# ESP8266_SMD_0603.net
KiCad netlist of a schematic drawn in EAGLE
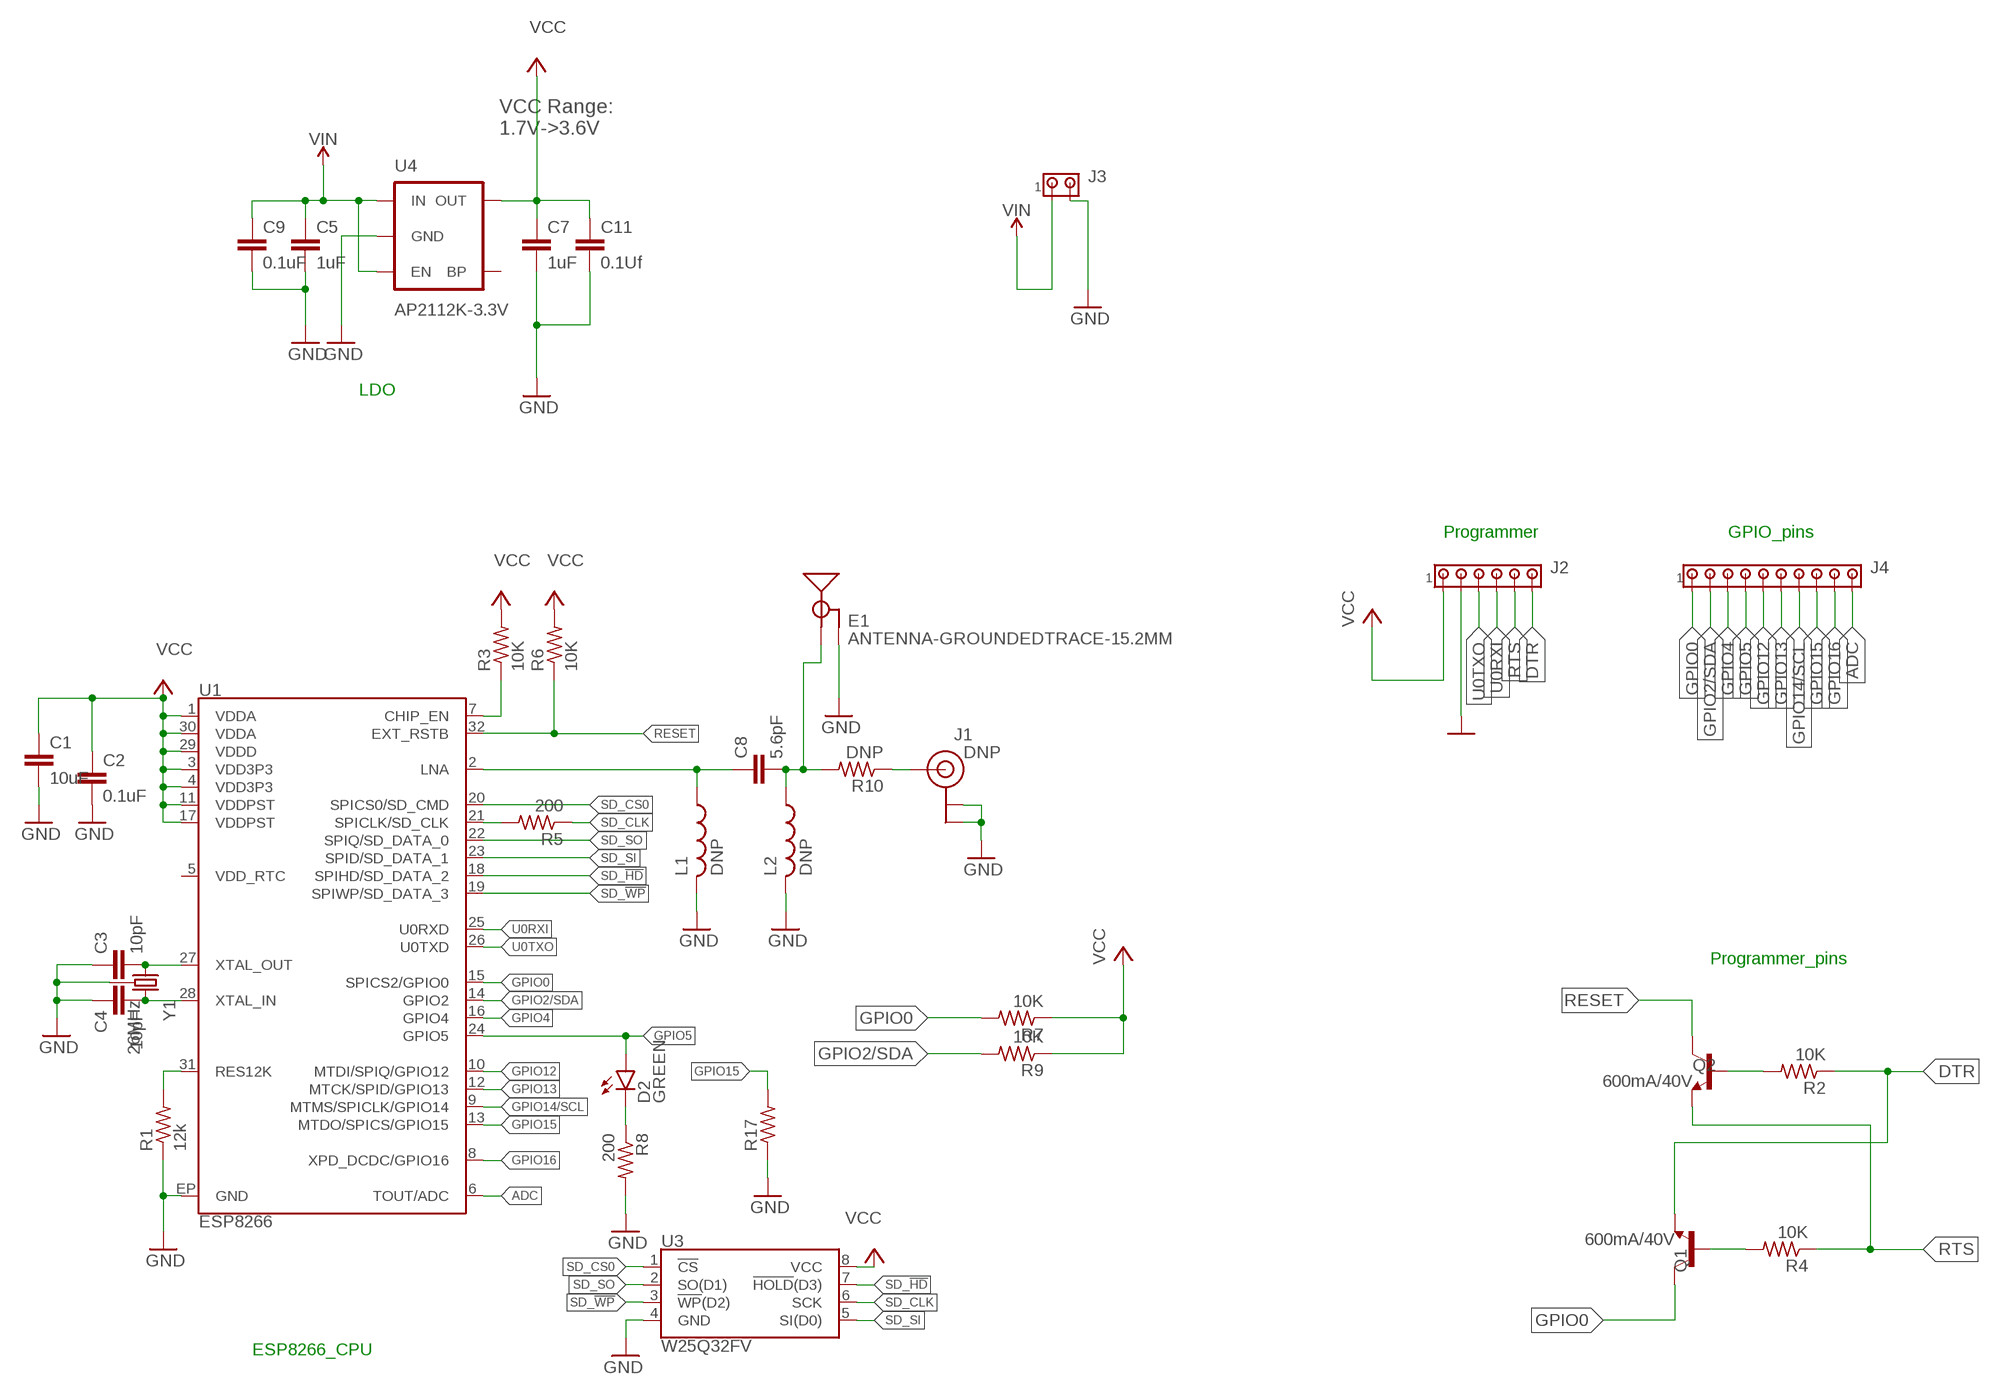
[diagram p0: schematic, sheet 1]

(export (version "E")
  (design (tool "Eeschema 10.0.6"))
  (components
    (comp (ref "C1")
      (value "10uF")
      (footprint "eagle-import:C0603")
      (libsource (lib "eagle-import") (part "resistor_C-EUC0603"))
    )
    (comp (ref "C2")
      (value "0.1uF")
      (footprint "eagle-import:C0603")
      (libsource (lib "eagle-import") (part "resistor_C-EUC0603"))
    )
    (comp (ref "C3")
      (value "10pF")
      (footprint "eagle-import:C0603")
      (libsource (lib "eagle-import") (part "C-EUC0603"))
    )
    (comp (ref "C4")
      (value "10pF")
      (footprint "eagle-import:C0603")
      (libsource (lib "eagle-import") (part "C-EUC0603"))
    )
    (comp (ref "C5")
      (value "1uF")
      (footprint "eagle-import:C0603")
      (libsource (lib "eagle-import") (part "C-EUC0603"))
    )
    (comp (ref "C7")
      (value "1uF")
      (footprint "eagle-import:C0603")
      (libsource (lib "eagle-import") (part "C-EUC0603"))
    )
    (comp (ref "C8")
      (value "5.6pF")
      (footprint "eagle-import:C0603")
      (libsource (lib "eagle-import") (part "C-EUC0603"))
    )
    (comp (ref "C9")
      (value "0.1uF")
      (footprint "eagle-import:C0603")
      (libsource (lib "eagle-import") (part "C-EUC0603"))
    )
    (comp (ref "C11")
      (value "0.1Uf")
      (footprint "eagle-import:C0603")
      (libsource (lib "eagle-import") (part "C-EUC0603"))
    )
    (comp (ref "D2")
      (value "GREEN")
      (footprint "eagle-import:LED-0603")
      (libsource (lib "eagle-import") (part "LED-GREEN0603"))
    )
    (comp (ref "E1")
      (value "ANTENNA-GROUNDEDTRACE-15.2MM")
      (footprint "eagle-import:TRACE_ANTENNA_2.4GHZ_15.2MM")
      (libsource (lib "eagle-import") (part "ANTENNA-GROUNDEDTRACE-15.2MM"))
    )
    (comp (ref "J1")
      (value "DNP")
      (footprint "eagle-import:U.FL")
      (libsource (lib "eagle-import") (part "U.FL"))
    )
    (comp (ref "J2")
      (value "MTA06-100")
      (footprint "eagle-import:10X06MTA")
      (libsource (lib "eagle-import") (part "MTA06-100"))
    )
    (comp (ref "J3")
      (value "MTA02-100")
      (footprint "eagle-import:10X02MTA")
      (libsource (lib "eagle-import") (part "MTA02-100"))
    )
    (comp (ref "J4")
      (value "MTA10-100")
      (footprint "eagle-import:10X10MTA")
      (libsource (lib "eagle-import") (part "MTA10-100"))
    )
    (comp (ref "L1")
      (value "DNP")
      (footprint "eagle-import:L0603")
      (libsource (lib "eagle-import") (part "L-USL0603"))
    )
    (comp (ref "L2")
      (value "DNP")
      (footprint "eagle-import:L0603")
      (libsource (lib "eagle-import") (part "L-USL0603"))
    )
    (comp (ref "Q1")
      (value "600mA/40V")
      (footprint "eagle-import:SOT23-3")
      (libsource (lib "eagle-import") (part "TRANS_NPN-MMBT2222AL"))
    )
    (comp (ref "Q2")
      (value "600mA/40V")
      (footprint "eagle-import:SOT23-3")
      (libsource (lib "eagle-import") (part "TRANS_NPN-MMBT2222AL"))
    )
    (comp (ref "R1")
      (value "12k")
      (footprint "eagle-import:R0603")
      (libsource (lib "eagle-import") (part "R-US_R0603"))
    )
    (comp (ref "R2")
      (value "10K")
      (footprint "eagle-import:R0603")
      (libsource (lib "eagle-import") (part "R-US_R0603"))
    )
    (comp (ref "R3")
      (value "10K")
      (footprint "eagle-import:R0603")
      (libsource (lib "eagle-import") (part "R-US_R0603"))
    )
    (comp (ref "R4")
      (value "10K")
      (footprint "eagle-import:R0603")
      (libsource (lib "eagle-import") (part "R-US_R0603"))
    )
    (comp (ref "R5")
      (value "200")
      (footprint "eagle-import:R0603")
      (libsource (lib "eagle-import") (part "R-US_R0603"))
    )
    (comp (ref "R6")
      (value "10K")
      (footprint "eagle-import:R0603")
      (libsource (lib "eagle-import") (part "R-US_R0603"))
    )
    (comp (ref "R7")
      (value "10K")
      (footprint "eagle-import:R0603")
      (libsource (lib "eagle-import") (part "R-US_R0603"))
    )
    (comp (ref "R8")
      (value "200")
      (footprint "eagle-import:R0603")
      (libsource (lib "eagle-import") (part "R-US_R0603"))
    )
    (comp (ref "R9")
      (value "10K")
      (footprint "eagle-import:R0603")
      (libsource (lib "eagle-import") (part "R-US_R0603"))
    )
    (comp (ref "R10")
      (value "DNP")
      (footprint "eagle-import:R0603")
      (libsource (lib "eagle-import") (part "R-US_R0603"))
    )
    (comp (ref "R17")
      (value "10K")
      (footprint "eagle-import:R0603")
      (libsource (lib "eagle-import") (part "R-US_R0603"))
    )
    (comp (ref "U1")
      (value "ESP8266")
      (footprint "eagle-import:QFN32")
      (libsource (lib "eagle-import") (part "ESP8266"))
    )
    (comp (ref "U3")
      (value "W25Q32FV")
      (footprint "eagle-import:SOIC-8")
      (libsource (lib "eagle-import") (part "W25Q32FVSS"))
    )
    (comp (ref "U4")
      (value "AP2112K-3.3V")
      (footprint "eagle-import:SOT23-5")
      (libsource (lib "eagle-import") (part "V_REG_LDOSMD"))
    )
    (comp (ref "Y1")
      (value "26MHz")
      (footprint "eagle-import:CRYSTAL-SMD-3.2X2.5")
      (libsource (lib "eagle-import") (part "CRYSTAL-GROUNDED3.2X2.5"))
    )
  )
  (nets
    (net (code "1") (name "/SD_~{HD}") (class "Default")
      (node (ref "U1") (pin "18") (pinfunction "SPIHD/SD_DATA_2_18") (pintype "bidirectional"))
      (node (ref "U3") (pin "7") (pinfunction "~{HOLD}(D3)_7") (pintype "bidirectional"))
    )
    (net (code "2") (name "/SD_~{WP}") (class "Default")
      (node (ref "U1") (pin "19") (pinfunction "SPIWP/SD_DATA_3_19") (pintype "bidirectional"))
      (node (ref "U3") (pin "3") (pinfunction "~{WP}(D2)_3") (pintype "bidirectional"))
    )
    (net (code "3") (name "ADC") (class "Default")
      (node (ref "J4") (pin "10") (pinfunction "10_10") (pintype "passive"))
      (node (ref "U1") (pin "6") (pinfunction "TOUT/ADC_6") (pintype "bidirectional"))
    )
    (net (code "4") (name "DTR") (class "Default")
      (node (ref "J2") (pin "6") (pinfunction "6_6") (pintype "passive"))
      (node (ref "Q1") (pin "2") (pinfunction "E_2") (pintype "passive"))
      (node (ref "R2") (pin "1") (pinfunction "1_1") (pintype "passive"))
    )
    (net (code "5") (name "GND") (class "Default")
      (node (ref "C1") (pin "2") (pinfunction "2_2") (pintype "passive"))
      (node (ref "C11") (pin "2") (pinfunction "2_2") (pintype "passive"))
      (node (ref "C2") (pin "2") (pinfunction "2_2") (pintype "passive"))
      (node (ref "C3") (pin "1") (pinfunction "1_1") (pintype "passive"))
      (node (ref "C4") (pin "1") (pinfunction "1_1") (pintype "passive"))
      (node (ref "C5") (pin "2") (pinfunction "2_2") (pintype "passive"))
      (node (ref "C7") (pin "2") (pinfunction "2_2") (pintype "passive"))
      (node (ref "C9") (pin "2") (pinfunction "2_2") (pintype "passive"))
      (node (ref "E1") (pin "GND") (pinfunction "GND_GND") (pintype "bidirectional"))
      (node (ref "J1") (pin "P$1") (pinfunction "GND_P$1") (pintype "bidirectional"))
      (node (ref "J1") (pin "P$2") (pinfunction "GND_P$2") (pintype "bidirectional"))
      (node (ref "J2") (pin "2") (pinfunction "2_2") (pintype "passive"))
      (node (ref "J3") (pin "2") (pinfunction "2_2") (pintype "passive"))
      (node (ref "L1") (pin "2") (pinfunction "2_2") (pintype "passive"))
      (node (ref "L2") (pin "2") (pinfunction "2_2") (pintype "passive"))
      (node (ref "R1") (pin "1") (pinfunction "1_1") (pintype "passive"))
      (node (ref "R17") (pin "1") (pinfunction "1_1") (pintype "passive"))
      (node (ref "R8") (pin "2") (pinfunction "2_2") (pintype "passive"))
      (node (ref "U1") (pin "EP") (pinfunction "GND_EP") (pintype "bidirectional"))
      (node (ref "U3") (pin "4") (pinfunction "GND_4") (pintype "bidirectional"))
      (node (ref "U4") (pin "2") (pinfunction "GND_2") (pintype "input"))
      (node (ref "Y1") (pin "2") (pinfunction "GND_2") (pintype "passive"))
      (node (ref "Y1") (pin "4") (pinfunction "GND_4") (pintype "passive"))
    )
    (net (code "6") (name "GPIO0") (class "Default")
      (node (ref "J4") (pin "1") (pinfunction "1_1") (pintype "passive"))
      (node (ref "Q1") (pin "3") (pinfunction "C_3") (pintype "passive"))
      (node (ref "R7") (pin "2") (pinfunction "2_2") (pintype "passive"))
      (node (ref "U1") (pin "15") (pinfunction "SPICS2/GPIO0_15") (pintype "bidirectional"))
    )
    (net (code "7") (name "GPIO2{slash}SDA") (class "Default")
      (node (ref "J4") (pin "2") (pinfunction "2_2") (pintype "passive"))
      (node (ref "R9") (pin "2") (pinfunction "2_2") (pintype "passive"))
      (node (ref "U1") (pin "14") (pinfunction "GPIO2_14") (pintype "bidirectional"))
    )
    (net (code "8") (name "GPIO4") (class "Default")
      (node (ref "J4") (pin "3") (pinfunction "3_3") (pintype "passive"))
      (node (ref "U1") (pin "16") (pinfunction "GPIO4_16") (pintype "bidirectional"))
    )
    (net (code "9") (name "GPIO5") (class "Default")
      (node (ref "D2") (pin "A") (pinfunction "A_A") (pintype "passive"))
      (node (ref "J4") (pin "4") (pinfunction "4_4") (pintype "passive"))
      (node (ref "U1") (pin "24") (pinfunction "GPIO5_24") (pintype "bidirectional"))
    )
    (net (code "10") (name "GPIO12") (class "Default")
      (node (ref "J4") (pin "5") (pinfunction "5_5") (pintype "passive"))
      (node (ref "U1") (pin "10") (pinfunction "MTDI/SPIQ/GPIO12_10") (pintype "bidirectional"))
    )
    (net (code "11") (name "GPIO13") (class "Default")
      (node (ref "J4") (pin "6") (pinfunction "6_6") (pintype "passive"))
      (node (ref "U1") (pin "12") (pinfunction "MTCK/SPID/GPIO13_12") (pintype "bidirectional"))
    )
    (net (code "12") (name "GPIO14{slash}SCL") (class "Default")
      (node (ref "J4") (pin "7") (pinfunction "7_7") (pintype "passive"))
      (node (ref "U1") (pin "9") (pinfunction "MTMS/SPICLK/GPIO14_9") (pintype "bidirectional"))
    )
    (net (code "13") (name "GPIO15") (class "Default")
      (node (ref "J4") (pin "8") (pinfunction "8_8") (pintype "passive"))
      (node (ref "R17") (pin "2") (pinfunction "2_2") (pintype "passive"))
      (node (ref "U1") (pin "13") (pinfunction "MTDO/SPICS/GPIO15_13") (pintype "bidirectional"))
    )
    (net (code "14") (name "GPIO16") (class "Default")
      (node (ref "J4") (pin "9") (pinfunction "9_9") (pintype "passive"))
      (node (ref "U1") (pin "8") (pinfunction "XPD_DCDC/GPIO16_8") (pintype "bidirectional"))
    )
    (net (code "15") (name "Net-(D2-PadC)") (class "Default")
      (node (ref "D2") (pin "C") (pinfunction "C_C") (pintype "passive"))
      (node (ref "R8") (pin "1") (pinfunction "1_1") (pintype "passive"))
    )
    (net (code "16") (name "Net-(E1-SIGNAL)") (class "Default")
      (node (ref "C8") (pin "2") (pinfunction "2_2") (pintype "passive"))
      (node (ref "E1") (pin "ANT") (pinfunction "SIGNAL_ANT") (pintype "bidirectional"))
      (node (ref "L2") (pin "1") (pinfunction "1_1") (pintype "passive"))
      (node (ref "R10") (pin "2") (pinfunction "2_2") (pintype "passive"))
    )
    (net (code "17") (name "Net-(J1-SIGNAL)") (class "Default")
      (node (ref "J1") (pin "P$3") (pinfunction "SIGNAL_P$3") (pintype "bidirectional"))
      (node (ref "R10") (pin "1") (pinfunction "1_1") (pintype "passive"))
    )
    (net (code "18") (name "Net-(Q1-B)") (class "Default")
      (node (ref "Q1") (pin "1") (pinfunction "B_1") (pintype "passive"))
      (node (ref "R4") (pin "2") (pinfunction "2_2") (pintype "passive"))
    )
    (net (code "19") (name "Net-(Q2-B)") (class "Default")
      (node (ref "Q2") (pin "1") (pinfunction "B_1") (pintype "passive"))
      (node (ref "R2") (pin "2") (pinfunction "2_2") (pintype "passive"))
    )
    (net (code "20") (name "Net-(U1-CHIP_EN)") (class "Default")
      (node (ref "R3") (pin "1") (pinfunction "1_1") (pintype "passive"))
      (node (ref "U1") (pin "7") (pinfunction "CHIP_EN_7") (pintype "bidirectional"))
    )
    (net (code "21") (name "Net-(U1-LNA)") (class "Default")
      (node (ref "C8") (pin "1") (pinfunction "1_1") (pintype "passive"))
      (node (ref "L1") (pin "1") (pinfunction "1_1") (pintype "passive"))
      (node (ref "U1") (pin "2") (pinfunction "LNA_2") (pintype "bidirectional"))
    )
    (net (code "22") (name "Net-(U1-RES12K)") (class "Default")
      (node (ref "R1") (pin "2") (pinfunction "2_2") (pintype "passive"))
      (node (ref "U1") (pin "31") (pinfunction "RES12K_31") (pintype "bidirectional"))
    )
    (net (code "23") (name "Net-(U1-SPICLK{slash}SD_CLK)") (class "Default")
      (node (ref "R5") (pin "2") (pinfunction "2_2") (pintype "passive"))
      (node (ref "U1") (pin "21") (pinfunction "SPICLK/SD_CLK_21") (pintype "bidirectional"))
    )
    (net (code "24") (name "Net-(U1-XTAL_IN)") (class "Default")
      (node (ref "C4") (pin "2") (pinfunction "2_2") (pintype "passive"))
      (node (ref "U1") (pin "28") (pinfunction "XTAL_IN_28") (pintype "bidirectional"))
      (node (ref "Y1") (pin "3") (pinfunction "2_3") (pintype "passive"))
    )
    (net (code "25") (name "Net-(U1-XTAL_OUT)") (class "Default")
      (node (ref "C3") (pin "2") (pinfunction "2_2") (pintype "passive"))
      (node (ref "U1") (pin "27") (pinfunction "XTAL_OUT_27") (pintype "bidirectional"))
      (node (ref "Y1") (pin "1") (pinfunction "1_1") (pintype "passive"))
    )
    (net (code "26") (name "RESET") (class "Default")
      (node (ref "Q2") (pin "3") (pinfunction "C_3") (pintype "passive"))
      (node (ref "R6") (pin "1") (pinfunction "1_1") (pintype "passive"))
      (node (ref "U1") (pin "32") (pinfunction "EXT_RSTB_32") (pintype "bidirectional"))
    )
    (net (code "27") (name "RTS") (class "Default")
      (node (ref "J2") (pin "5") (pinfunction "5_5") (pintype "passive"))
      (node (ref "Q2") (pin "2") (pinfunction "E_2") (pintype "passive"))
      (node (ref "R4") (pin "1") (pinfunction "1_1") (pintype "passive"))
    )
    (net (code "28") (name "SD_CLK") (class "Default")
      (node (ref "R5") (pin "1") (pinfunction "1_1") (pintype "passive"))
      (node (ref "U3") (pin "6") (pinfunction "SCK_6") (pintype "bidirectional"))
    )
    (net (code "29") (name "SD_CS0") (class "Default")
      (node (ref "U1") (pin "20") (pinfunction "SPICS0/SD_CMD_20") (pintype "bidirectional"))
      (node (ref "U3") (pin "1") (pinfunction "~{CS}_1") (pintype "bidirectional"))
    )
    (net (code "30") (name "SD_SI") (class "Default")
      (node (ref "U1") (pin "23") (pinfunction "SPID/SD_DATA_1_23") (pintype "bidirectional"))
      (node (ref "U3") (pin "5") (pinfunction "SI(D0)_5") (pintype "bidirectional"))
    )
    (net (code "31") (name "SD_SO") (class "Default")
      (node (ref "U1") (pin "22") (pinfunction "SPIQ/SD_DATA_0_22") (pintype "bidirectional"))
      (node (ref "U3") (pin "2") (pinfunction "SO(D1)_2") (pintype "bidirectional"))
    )
    (net (code "32") (name "U0RXI") (class "Default")
      (node (ref "J2") (pin "4") (pinfunction "4_4") (pintype "passive"))
      (node (ref "U1") (pin "25") (pinfunction "U0RXD_25") (pintype "bidirectional"))
    )
    (net (code "33") (name "U0TXO") (class "Default")
      (node (ref "J2") (pin "3") (pinfunction "3_3") (pintype "passive"))
      (node (ref "U1") (pin "26") (pinfunction "U0TXD_26") (pintype "bidirectional"))
    )
    (net (code "34") (name "VCC") (class "Default")
      (node (ref "C1") (pin "1") (pinfunction "1_1") (pintype "passive"))
      (node (ref "C11") (pin "1") (pinfunction "1_1") (pintype "passive"))
      (node (ref "C2") (pin "1") (pinfunction "1_1") (pintype "passive"))
      (node (ref "C7") (pin "1") (pinfunction "1_1") (pintype "passive"))
      (node (ref "J2") (pin "1") (pinfunction "1_1") (pintype "passive"))
      (node (ref "R3") (pin "2") (pinfunction "2_2") (pintype "passive"))
      (node (ref "R6") (pin "2") (pinfunction "2_2") (pintype "passive"))
      (node (ref "R7") (pin "1") (pinfunction "1_1") (pintype "passive"))
      (node (ref "R9") (pin "1") (pinfunction "1_1") (pintype "passive"))
      (node (ref "U1") (pin "1") (pinfunction "VDDA_1") (pintype "bidirectional"))
      (node (ref "U1") (pin "11") (pinfunction "VDDPST_11") (pintype "bidirectional"))
      (node (ref "U1") (pin "17") (pinfunction "VDDPST_17") (pintype "bidirectional"))
      (node (ref "U1") (pin "29") (pinfunction "VDDD_29") (pintype "bidirectional"))
      (node (ref "U1") (pin "3") (pinfunction "VDD3P3_3") (pintype "bidirectional"))
      (node (ref "U1") (pin "30") (pinfunction "VDDA_30") (pintype "bidirectional"))
      (node (ref "U1") (pin "4") (pinfunction "VDD3P3_4") (pintype "bidirectional"))
      (node (ref "U3") (pin "8") (pinfunction "VCC_8") (pintype "bidirectional"))
      (node (ref "U4") (pin "5") (pinfunction "OUT_5") (pintype "passive"))
    )
    (net (code "35") (name "VIN") (class "Default")
      (node (ref "C5") (pin "1") (pinfunction "1_1") (pintype "passive"))
      (node (ref "C9") (pin "1") (pinfunction "1_1") (pintype "passive"))
      (node (ref "J3") (pin "1") (pinfunction "1_1") (pintype "passive"))
      (node (ref "U4") (pin "1") (pinfunction "IN_1") (pintype "input"))
      (node (ref "U4") (pin "3") (pinfunction "EN_3") (pintype "input"))
    )
    (net (code "36") (name "unconnected-(U1-VDD_RTC-Pad5)") (class "Default")
      (node (ref "U1") (pin "5") (pinfunction "VDD_RTC_5") (pintype "bidirectional"))
    )
    (net (code "37") (name "unconnected-(U4-BP-Pad4)") (class "Default")
      (node (ref "U4") (pin "4") (pinfunction "BP_4") (pintype "input"))
    )
  )
)
